# Intar_Vibration_Module.net
KiCad netlist of a schematic drawn in EAGLE
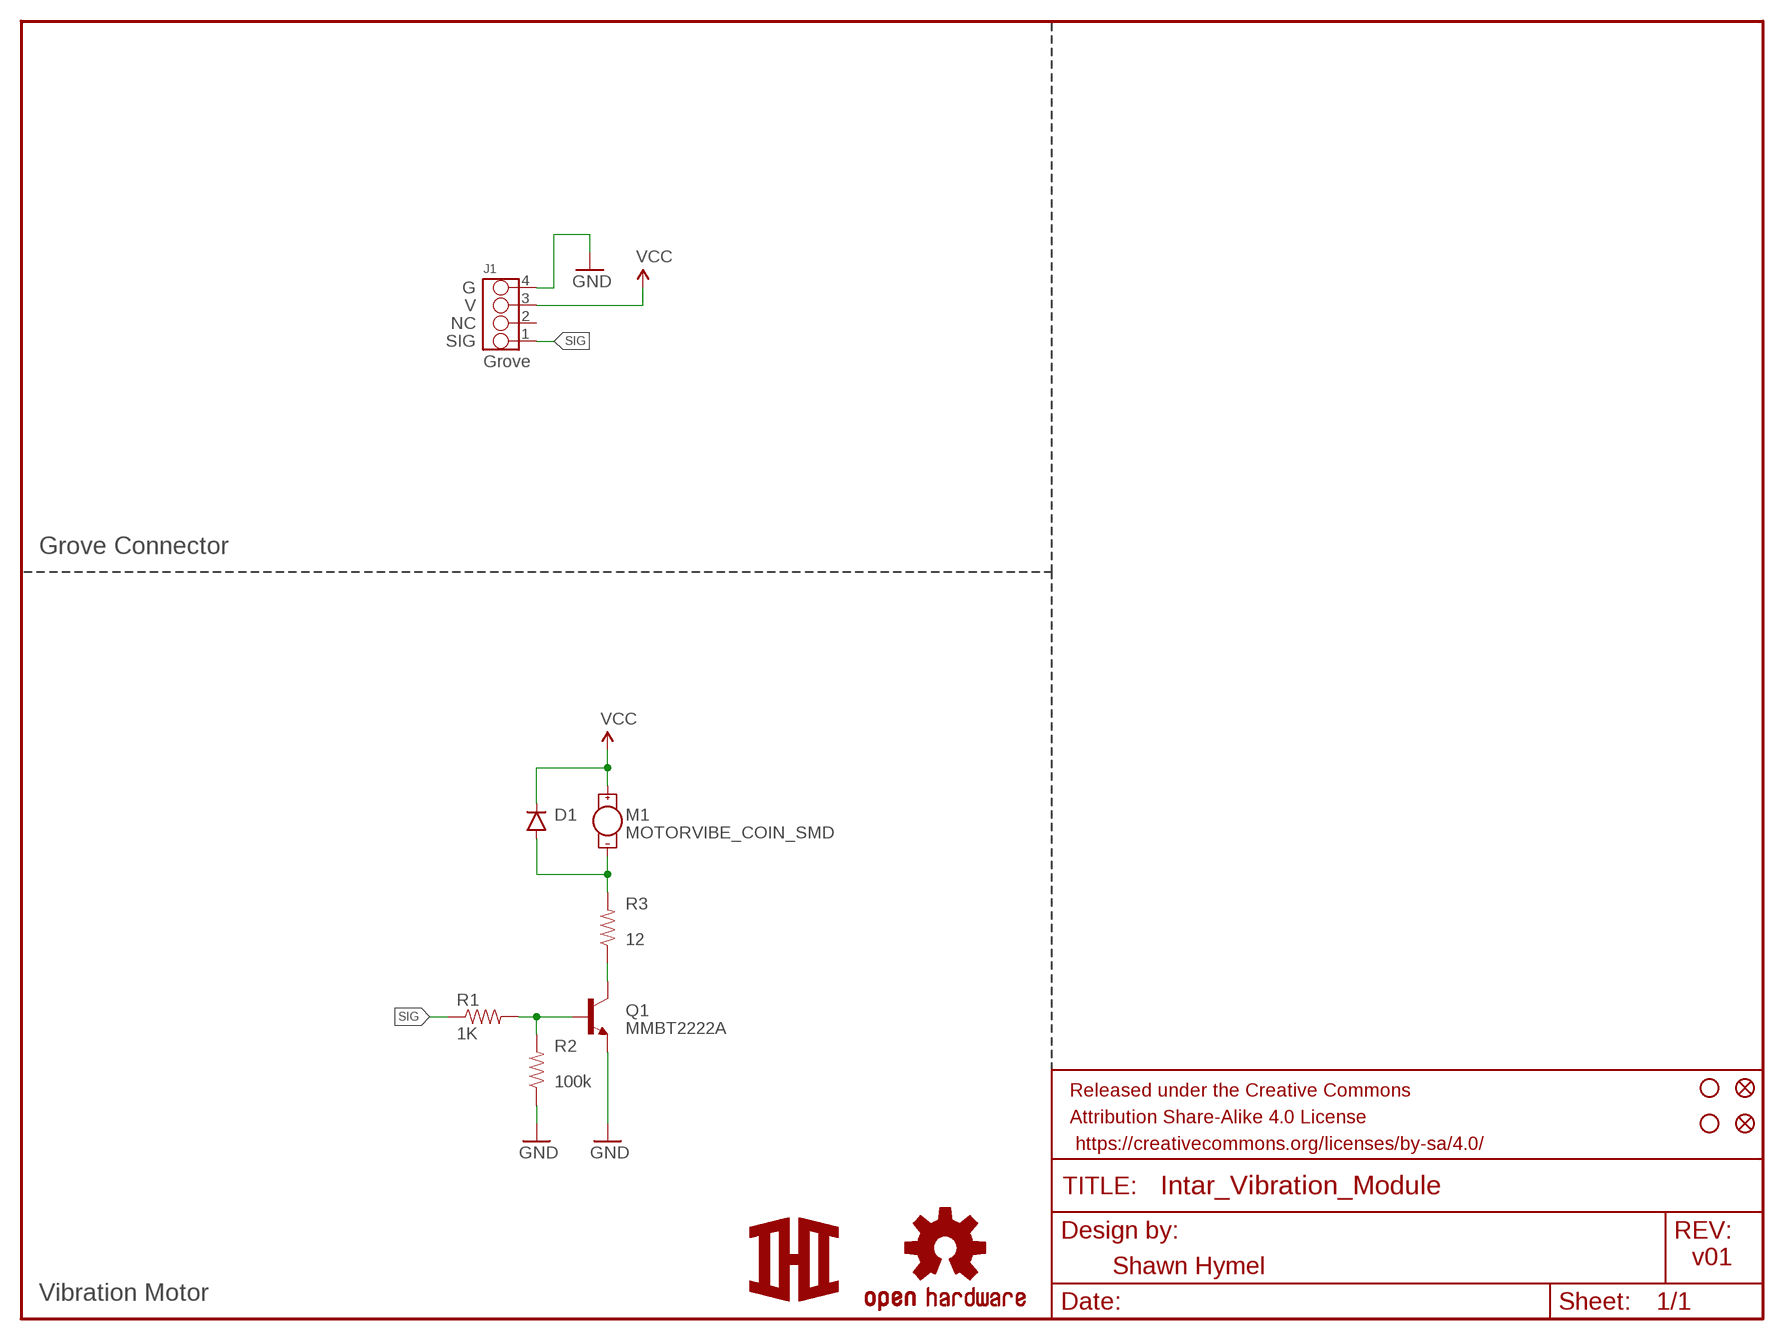
[diagram p0: schematic, sheet 1]

(export (version "E")
  (design (tool "Eeschema 10.0.6"))
  (components
    (comp (ref "D1")
      (value "250mA/100V")
      (footprint "eagle-import:SOD-323")
      (libsource (lib "eagle-import") (part "DIODEBAS16"))
    )
    (comp (ref "FID1")
      (value "FIDUCIAL1X2")
      (footprint "eagle-import:FIDUCIAL-1X2")
      (libsource (lib "eagle-import") (part "FIDUCIAL1X2"))
    )
    (comp (ref "FID2")
      (value "FIDUCIAL1X2")
      (footprint "eagle-import:FIDUCIAL-1X2")
      (libsource (lib "eagle-import") (part "FIDUCIAL1X2"))
    )
    (comp (ref "FRAME1")
      (value "FRAME-LETTER")
      (footprint "eagle-import:CREATIVE_COMMONS")
      (libsource (lib "eagle-import") (part "FRAME-LETTER"))
    )
    (comp (ref "J1")
      (value "GROVE-4P-2.0-3470130P1")
      (footprint "eagle-import:4P-2.0")
      (libsource (lib "eagle-import") (part "GROVE-4P-2.0-3470130P1"))
    )
    (comp (ref "LOGO1")
      (value "OSHW-LOGOS")
      (footprint "eagle-import:OSHW-LOGO-S")
      (libsource (lib "eagle-import") (part "OSHW-LOGOS"))
    )
    (comp (ref "M1")
      (value "MOTORVIBE_COIN_SMD")
      (footprint "eagle-import:VIBE_COIN_SMD")
      (libsource (lib "eagle-import") (part "MOTORVIBE_COIN_SMD"))
    )
    (comp (ref "Q1")
      (value "MMBT2222A")
      (footprint "eagle-import:SOT23-3")
      (libsource (lib "eagle-import") (part "TRANSISTOR_NPNMMBT2222A"))
    )
    (comp (ref "R1")
      (value "1K")
      (footprint "eagle-import:0603-RES")
      (libsource (lib "eagle-import") (part "1KOHM-1/10W-1%(0603)"))
    )
    (comp (ref "R2")
      (value "100k")
      (footprint "eagle-import:0603-RES")
      (libsource (lib "eagle-import") (part "100KOHM-1/10W-1%(0603)"))
    )
    (comp (ref "R3")
      (value "12")
      (footprint "eagle-import:0603-RES")
      (libsource (lib "eagle-import") (part "RESISTOR0603"))
    )
    (comp (ref "STANDOFF1")
      (value "STAND-OFF")
      (footprint "eagle-import:STAND-OFF")
      (libsource (lib "eagle-import") (part "STAND-OFF"))
    )
    (comp (ref "STANDOFF2")
      (value "STAND-OFF")
      (footprint "eagle-import:STAND-OFF")
      (libsource (lib "eagle-import") (part "STAND-OFF"))
    )
    (comp (ref "U$1")
      (value "LOGOSM")
      (footprint "eagle-import:LOGO_SM")
      (libsource (lib "eagle-import") (part "LOGOSM"))
    )
  )
  (nets
    (net (code "1") (name "GND") (class "Default")
      (node (ref "J1") (pin "4") (pinfunction "4_4") (pintype "bidirectional"))
      (node (ref "Q1") (pin "2") (pinfunction "E_2") (pintype "passive"))
      (node (ref "R2") (pin "1") (pinfunction "1_1") (pintype "passive"))
    )
    (net (code "2") (name "Net-(M1--)") (class "Default")
      (node (ref "D1") (pin "A") (pinfunction "A_A") (pintype "passive"))
      (node (ref "M1") (pin "2") (pinfunction "-_2") (pintype "bidirectional"))
      (node (ref "R3") (pin "2") (pinfunction "2_2") (pintype "passive"))
    )
    (net (code "3") (name "Net-(Q1-B)") (class "Default")
      (node (ref "Q1") (pin "1") (pinfunction "B_1") (pintype "passive"))
      (node (ref "R1") (pin "2") (pinfunction "2_2") (pintype "passive"))
      (node (ref "R2") (pin "2") (pinfunction "2_2") (pintype "passive"))
    )
    (net (code "4") (name "Net-(Q1-C)") (class "Default")
      (node (ref "Q1") (pin "3") (pinfunction "C_3") (pintype "passive"))
      (node (ref "R3") (pin "1") (pinfunction "1_1") (pintype "passive"))
    )
    (net (code "5") (name "SIG") (class "Default")
      (node (ref "J1") (pin "1") (pinfunction "1_1") (pintype "bidirectional"))
      (node (ref "R1") (pin "1") (pinfunction "1_1") (pintype "passive"))
    )
    (net (code "6") (name "VCC") (class "Default")
      (node (ref "D1") (pin "C") (pinfunction "C_C") (pintype "passive"))
      (node (ref "J1") (pin "3") (pinfunction "3_3") (pintype "bidirectional"))
      (node (ref "M1") (pin "1") (pinfunction "+_1") (pintype "bidirectional"))
    )
    (net (code "7") (name "unconnected-(J1-Pad2)") (class "Default")
      (node (ref "J1") (pin "2") (pinfunction "2_2") (pintype "bidirectional"))
    )
  )
)
